# SCH_2ND-Try-555_2025-10-18.net
KiCad netlist of a schematic drawn in EasyEDA
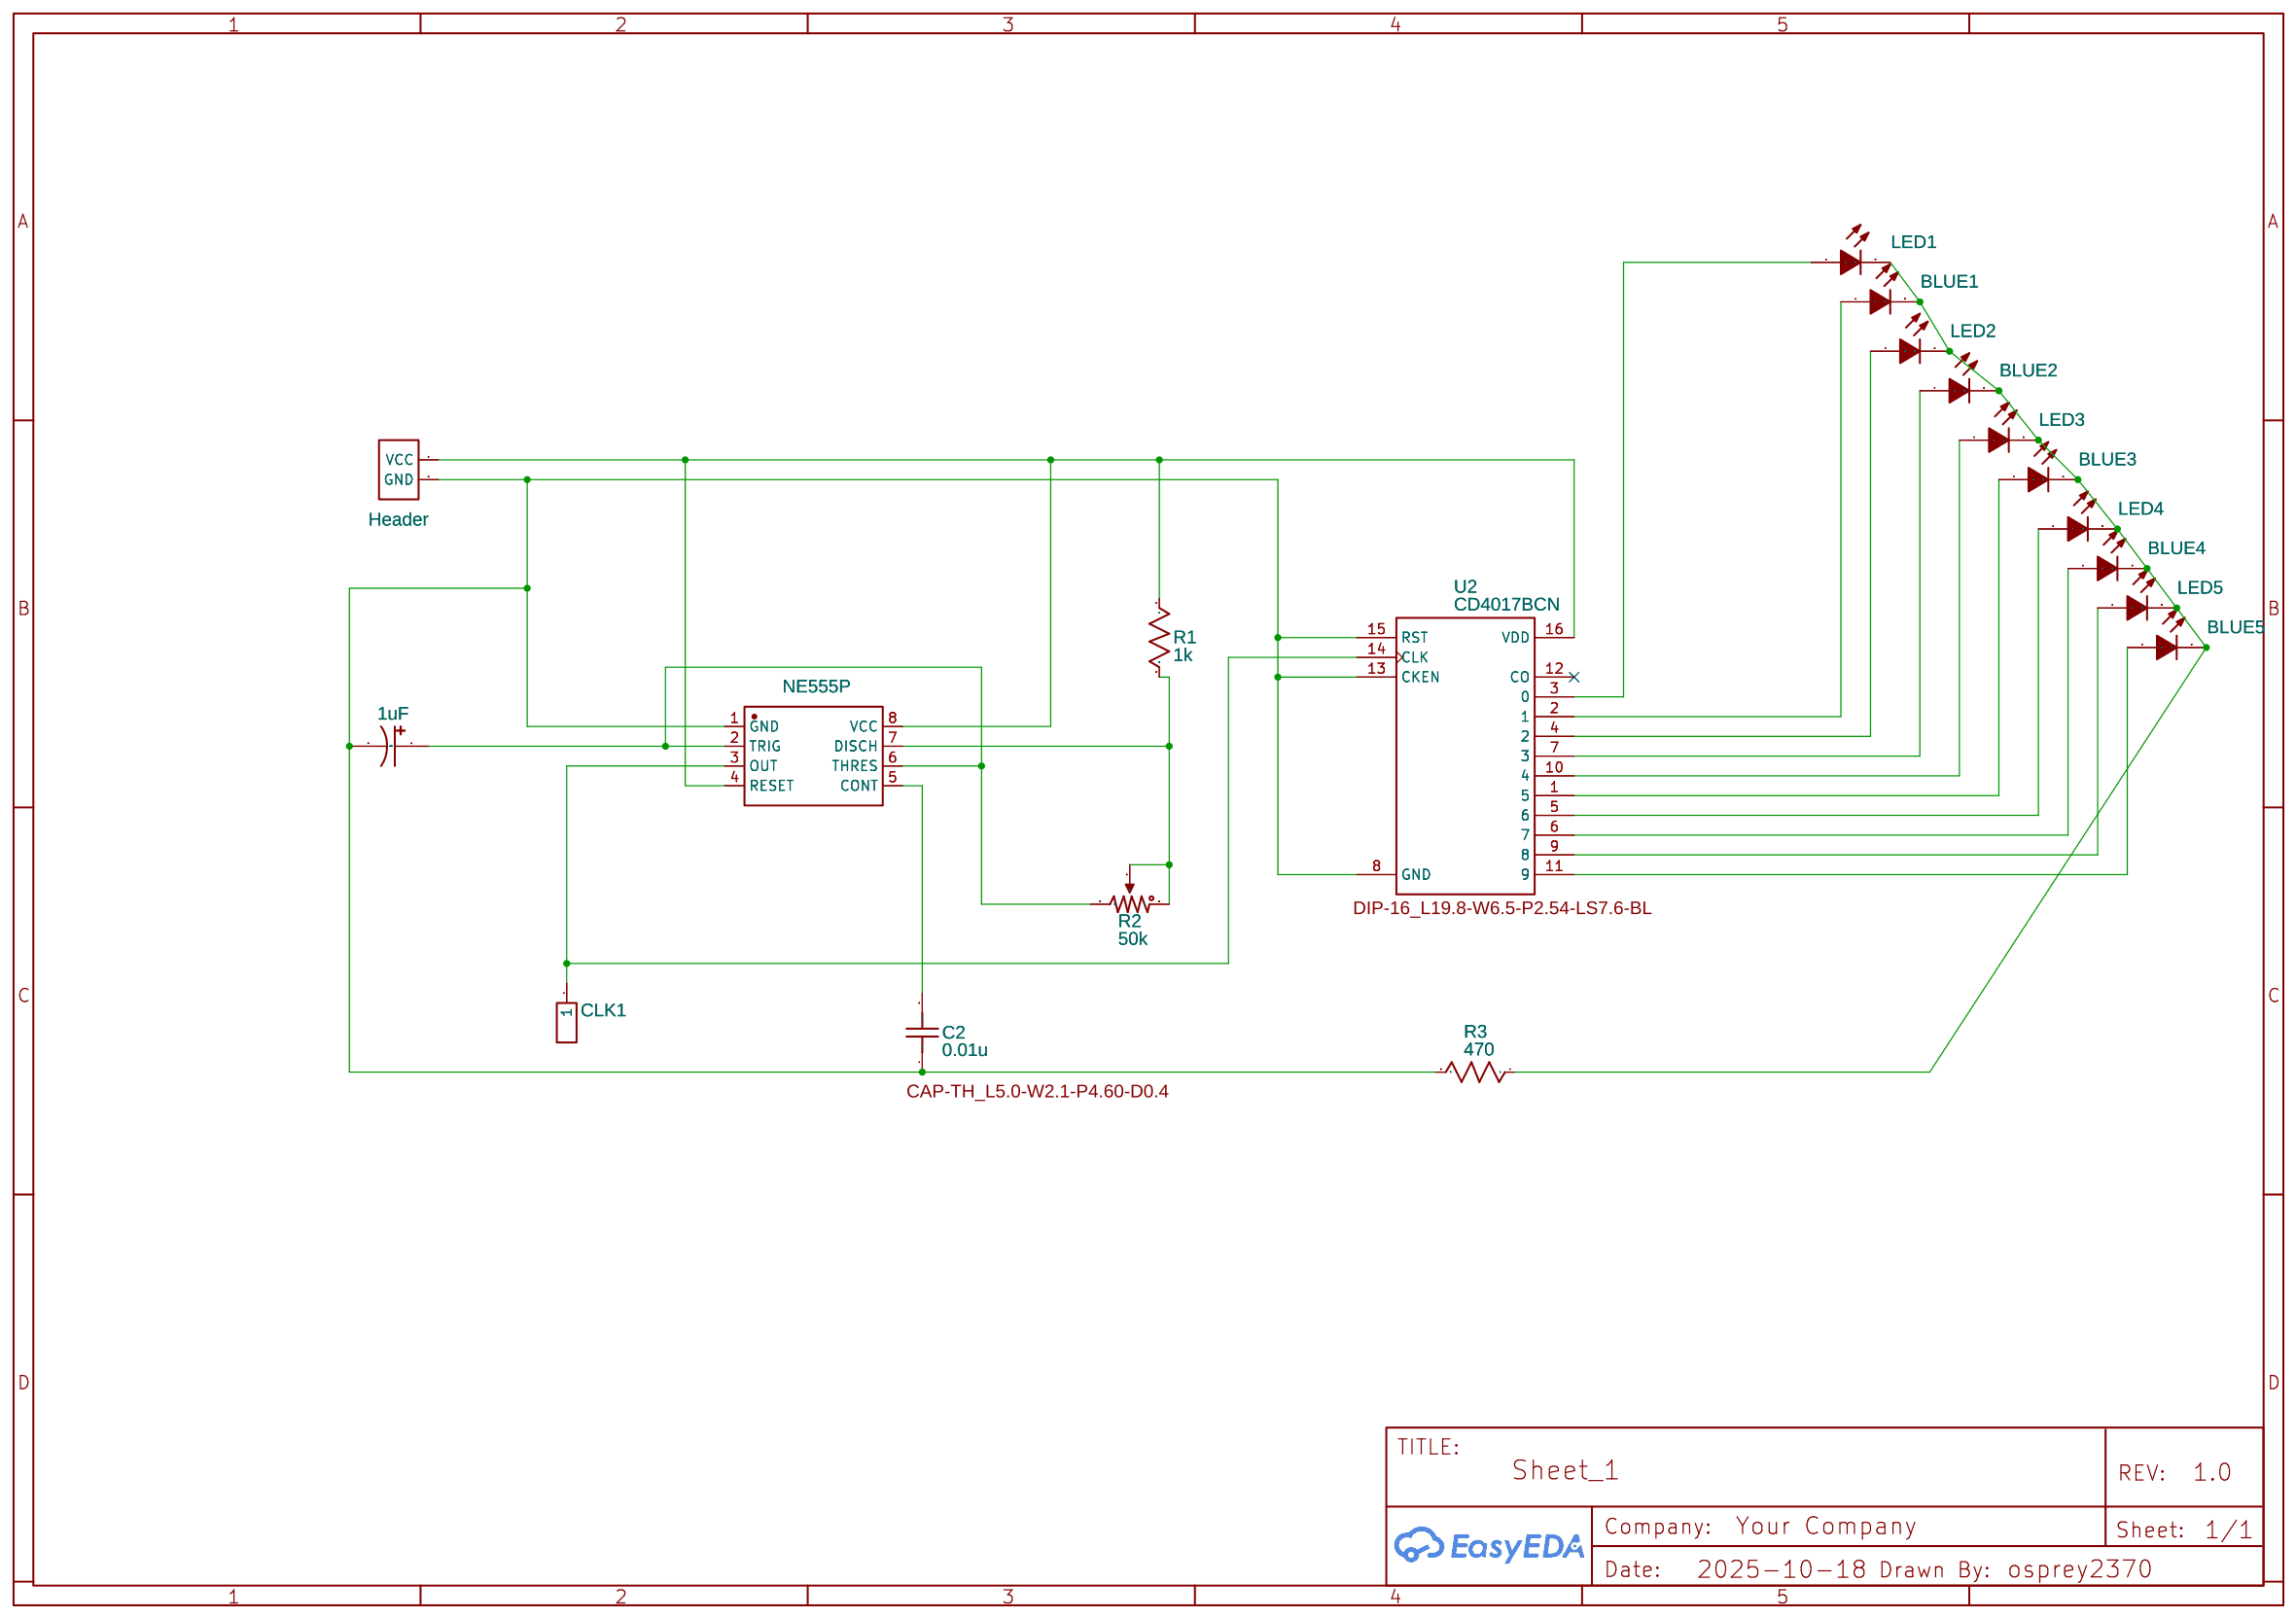
[diagram p0: schematic sheet]

(export (version "E")
  (design (tool "Eeschema 10.0.6"))
  (components
    (comp (ref "BLUE1") (value "LED_5MM") (libsource (lib "") (part "LED_5MM")))
    (comp (ref "BLUE2") (value "LED_5MM") (libsource (lib "") (part "LED_5MM")))
    (comp (ref "BLUE3") (value "LED_5MM") (libsource (lib "") (part "LED_5MM")))
    (comp (ref "BLUE4") (value "LED_5MM") (libsource (lib "") (part "LED_5MM")))
    (comp (ref "BLUE5") (value "LED_5MM") (libsource (lib "") (part "LED_5MM")))
    (comp (ref "C1")
      (value "1uF")
      (fields (field (name "Manufacturer Part") "UVZ1H010MDD") (field (name "Manufacturer") "Nichicon(尼吉康)"))
      (libsource (lib "") (part "UVZ1H010MDD"))
    )
    (comp (ref "C2") (value "0.01u") (libsource (lib "") (part "C_0603_US")))
    (comp (ref "CLK1")
      (value "C81276")
      (fields
        (field (name "Manufacturer Part") "2.54-1*1P针")
        (field (name "Manufacturer") "BOOMELE(Boom Precision Elec)")
      )
      (libsource (lib "") (part "Header-Male-2.54_1x1"))
    )
    (comp (ref "H1") (value "Header") (libsource (lib "") (part "HEADER-FEMALE-2.54_1X2")))
    (comp (ref "LED1") (value "LED_5MM") (libsource (lib "") (part "LED_5MM_1")))
    (comp (ref "LED2") (value "LED_5MM") (libsource (lib "") (part "LED_5MM_1")))
    (comp (ref "LED3") (value "LED_5MM") (libsource (lib "") (part "LED_5MM_1")))
    (comp (ref "LED4") (value "LED_5MM") (libsource (lib "") (part "LED_5MM_1")))
    (comp (ref "LED5") (value "LED_5MM") (libsource (lib "") (part "LED_5MM_1")))
    (comp (ref "R1")
      (value "1k")
      (fields (field (name "Manufacturer Part") "?"))
      (libsource (lib "") (part "Resistor"))
    )
    (comp (ref "R2")
      (value "50k")
      (fields (field (name "Manufacturer Part") "?"))
      (libsource (lib "") (part "Potentiometer"))
    )
    (comp (ref "R3")
      (value "470")
      (fields (field (name "Manufacturer Part") "?"))
      (libsource (lib "") (part "Resistor_1"))
    )
    (comp (ref "U1")
      (value "NE555P")
      (fields (field (name "Manufacturer") "TI(德州仪器)"))
      (libsource (lib "") (part "NE555P"))
    )
    (comp (ref "U2") (value "CD4017BCN") (libsource (lib "") (part "CD4017BCN")))
  )
  (nets
    (net (code "1") (name "Net-(BLUE1-A)") (class "Default")
      (node (ref "BLUE1") (pin "1") (pinfunction "A_1") (pintype "input"))
      (node (ref "U2") (pin "2") (pinfunction "1_2") (pintype "output"))
    )
    (net (code "2") (name "Net-(BLUE1-K)") (class "Default")
      (node (ref "BLUE1") (pin "2") (pinfunction "K_2") (pintype "input"))
      (node (ref "BLUE2") (pin "2") (pinfunction "K_2") (pintype "input"))
      (node (ref "BLUE3") (pin "2") (pinfunction "K_2") (pintype "input"))
      (node (ref "BLUE4") (pin "2") (pinfunction "K_2") (pintype "input"))
      (node (ref "BLUE5") (pin "2") (pinfunction "K_2") (pintype "input"))
      (node (ref "LED1") (pin "2") (pinfunction "K_2") (pintype "input"))
      (node (ref "LED2") (pin "2") (pinfunction "K_2") (pintype "input"))
      (node (ref "LED3") (pin "2") (pinfunction "K_2") (pintype "input"))
      (node (ref "LED4") (pin "2") (pinfunction "K_2") (pintype "input"))
      (node (ref "LED5") (pin "2") (pinfunction "K_2") (pintype "input"))
      (node (ref "R3") (pin "1") (pinfunction "1_1") (pintype "unspecified"))
    )
    (net (code "3") (name "Net-(BLUE2-A)") (class "Default")
      (node (ref "BLUE2") (pin "1") (pinfunction "A_1") (pintype "input"))
      (node (ref "U2") (pin "7") (pinfunction "3_7") (pintype "output"))
    )
    (net (code "4") (name "Net-(BLUE3-A)") (class "Default")
      (node (ref "BLUE3") (pin "1") (pinfunction "A_1") (pintype "input"))
      (node (ref "U2") (pin "1") (pinfunction "5_1") (pintype "output"))
    )
    (net (code "5") (name "Net-(BLUE4-A)") (class "Default")
      (node (ref "BLUE4") (pin "1") (pinfunction "A_1") (pintype "input"))
      (node (ref "U2") (pin "6") (pinfunction "7_6") (pintype "output"))
    )
    (net (code "6") (name "Net-(BLUE5-A)") (class "Default")
      (node (ref "BLUE5") (pin "1") (pinfunction "A_1") (pintype "input"))
      (node (ref "U2") (pin "11") (pinfunction "9_11") (pintype "output"))
    )
    (net (code "7") (name "Net-(H1-GND)") (class "Default")
      (node (ref "C1") (pin "2") (pinfunction "2_2") (pintype "unspecified"))
      (node (ref "C2") (pin "1") (pinfunction "1_1") (pintype "unspecified"))
      (node (ref "H1") (pin "2") (pinfunction "GND_2") (pintype "unspecified"))
      (node (ref "R3") (pin "2") (pinfunction "2_2") (pintype "unspecified"))
      (node (ref "U1") (pin "1") (pinfunction "GND_1") (pintype "unspecified"))
      (node (ref "U2") (pin "13") (pinfunction "CKEN_13") (pintype "unspecified"))
      (node (ref "U2") (pin "15") (pinfunction "RST_15") (pintype "unspecified"))
      (node (ref "U2") (pin "8") (pinfunction "GND_8") (pintype "passive"))
    )
    (net (code "8") (name "Net-(H1-VCC)") (class "Default")
      (node (ref "H1") (pin "1") (pinfunction "VCC_1") (pintype "unspecified"))
      (node (ref "R1") (pin "1") (pinfunction "1_1") (pintype "unspecified"))
      (node (ref "U1") (pin "4") (pinfunction "RESET_4") (pintype "unspecified"))
      (node (ref "U1") (pin "8") (pinfunction "VCC_8") (pintype "unspecified"))
      (node (ref "U2") (pin "16") (pinfunction "VDD_16") (pintype "passive"))
    )
    (net (code "9") (name "Net-(LED1-A)") (class "Default")
      (node (ref "LED1") (pin "1") (pinfunction "A_1") (pintype "input"))
      (node (ref "U2") (pin "3") (pinfunction "0_3") (pintype "output"))
    )
    (net (code "10") (name "Net-(LED2-A)") (class "Default")
      (node (ref "LED2") (pin "1") (pinfunction "A_1") (pintype "input"))
      (node (ref "U2") (pin "4") (pinfunction "2_4") (pintype "output"))
    )
    (net (code "11") (name "Net-(LED3-A)") (class "Default")
      (node (ref "LED3") (pin "1") (pinfunction "A_1") (pintype "input"))
      (node (ref "U2") (pin "10") (pinfunction "4_10") (pintype "output"))
    )
    (net (code "12") (name "Net-(LED4-A)") (class "Default")
      (node (ref "LED4") (pin "1") (pinfunction "A_1") (pintype "input"))
      (node (ref "U2") (pin "5") (pinfunction "6_5") (pintype "output"))
    )
    (net (code "13") (name "Net-(LED5-A)") (class "Default")
      (node (ref "LED5") (pin "1") (pinfunction "A_1") (pintype "input"))
      (node (ref "U2") (pin "9") (pinfunction "8_9") (pintype "output"))
    )
    (net (code "14") (name "Net-(R2-2)") (class "Default")
      (node (ref "R1") (pin "2") (pinfunction "2_2") (pintype "unspecified"))
      (node (ref "R2") (pin "2") (pinfunction "3_2") (pintype "unspecified"))
      (node (ref "R2") (pin "3") (pinfunction "2_3") (pintype "unspecified"))
      (node (ref "U1") (pin "7") (pinfunction "DISCH_7") (pintype "unspecified"))
    )
    (net (code "15") (name "Net-(U1-CONT)") (class "Default")
      (node (ref "C2") (pin "2") (pinfunction "2_2") (pintype "unspecified"))
      (node (ref "U1") (pin "5") (pinfunction "CONT_5") (pintype "unspecified"))
    )
    (net (code "16") (name "Net-(U1-OUT)") (class "Default")
      (node (ref "CLK1") (pin "1") (pinfunction "1_1") (pintype "unspecified"))
      (node (ref "U1") (pin "3") (pinfunction "OUT_3") (pintype "unspecified"))
      (node (ref "U2") (pin "14") (pinfunction "CLK_14") (pintype "unspecified"))
    )
    (net (code "17") (name "Net-(U1-THRES)") (class "Default")
      (node (ref "C1") (pin "1") (pinfunction "1_1") (pintype "unspecified"))
      (node (ref "R2") (pin "1") (pinfunction "1_1") (pintype "unspecified"))
      (node (ref "U1") (pin "2") (pinfunction "TRIG_2") (pintype "unspecified"))
      (node (ref "U1") (pin "6") (pinfunction "THRES_6") (pintype "unspecified"))
    )
    (net (code "18") (name "unconnected-(U2-CO-Pad12)") (class "Default")
      (node (ref "U2") (pin "12") (pinfunction "CO_12") (pintype "output+no_connect"))
    )
  )
)
